# UPS.net
KiCad netlist of a schematic drawn in Altium Designer
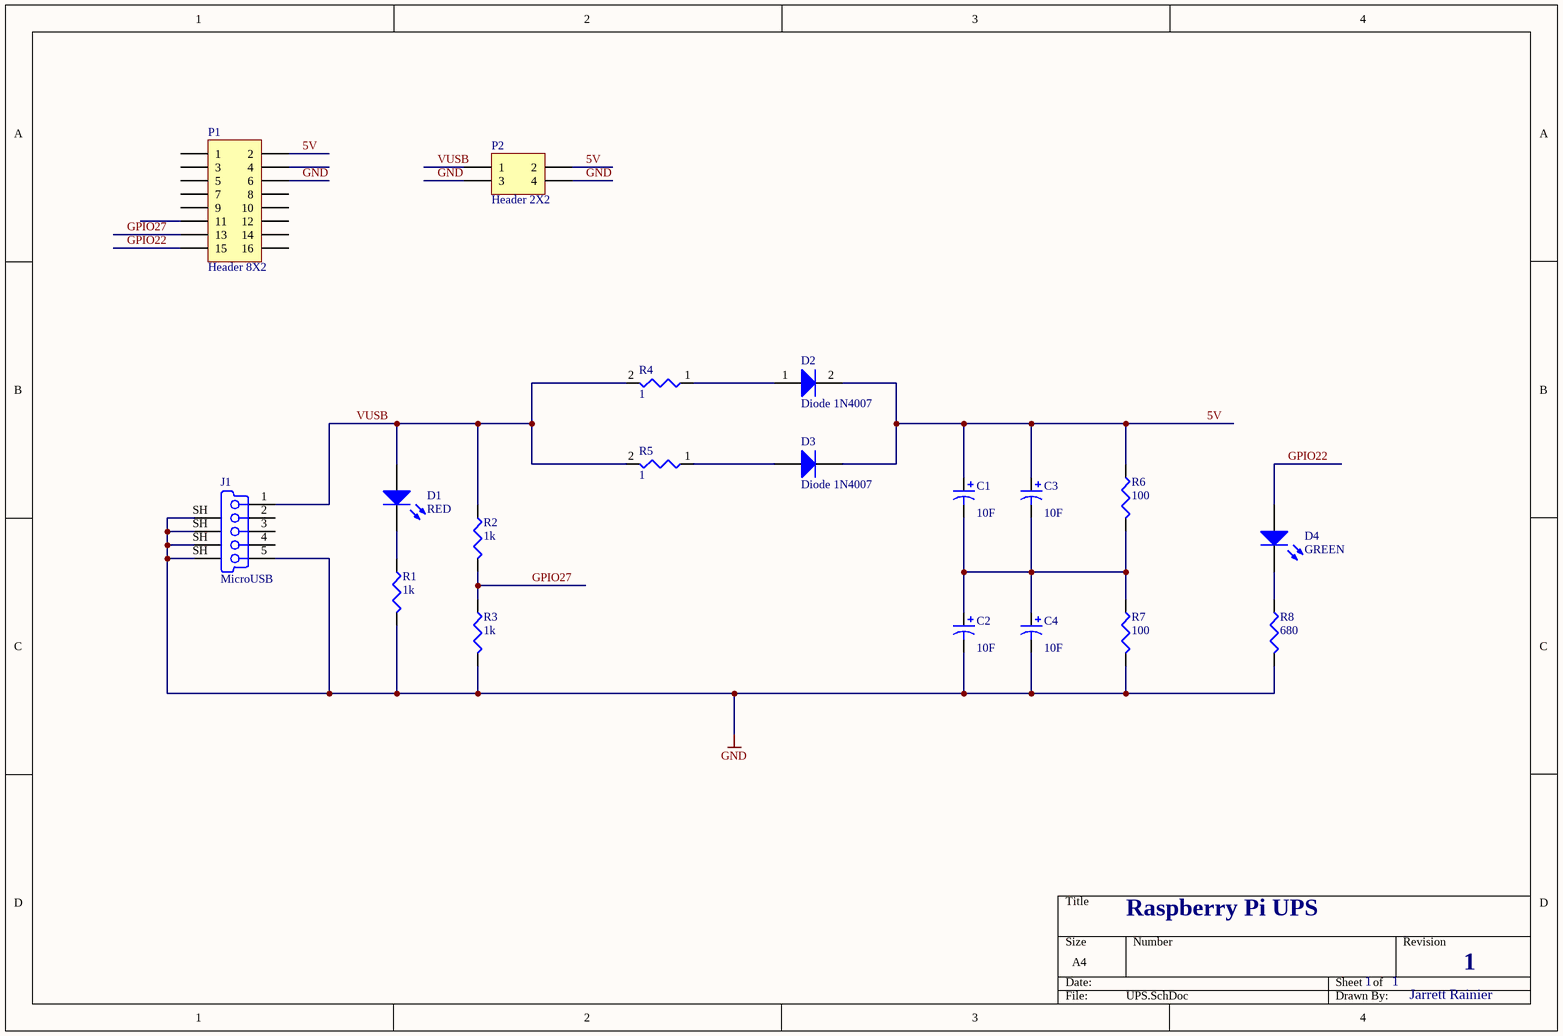
[diagram p0: UPS.SchDoc]

(export (version "E")
  (design (tool "Eeschema 10.0.6"))
  (components
    (comp (ref "C1")
      (value "10F")
      (footprint "CAPE5.0mm")
      (description "Polarized Capacitor (Radial)")
      (fields (field (name "Comment") "Cap Pol1") (field (name "PUBLISHER") "Altium Limited"))
      (libsource (lib "Miscellaneous Devices") (part "Cap Pol1"))
    )
    (comp (ref "C2")
      (value "10F")
      (footprint "CAPE5.0mm")
      (description "Polarized Capacitor (Radial)")
      (fields (field (name "Comment") "Cap Pol1") (field (name "PUBLISHER") "Altium Limited"))
      (libsource (lib "Miscellaneous Devices") (part "Cap Pol1"))
    )
    (comp (ref "C3")
      (value "10F")
      (footprint "CAPE5.0mm")
      (description "Polarized Capacitor (Radial)")
      (fields (field (name "Comment") "Cap Pol1") (field (name "PUBLISHER") "Altium Limited"))
      (libsource (lib "Miscellaneous Devices") (part "Cap Pol1"))
    )
    (comp (ref "C4")
      (value "10F")
      (footprint "CAPE5.0mm")
      (description "Polarized Capacitor (Radial)")
      (fields (field (name "Comment") "Cap Pol1") (field (name "PUBLISHER") "Altium Limited"))
      (libsource (lib "Miscellaneous Devices") (part "Cap Pol1"))
    )
    (comp (ref "D1")
      (value "RED")
      (footprint "LED_3mm")
      (description "Typical INFRARED GaAs LED")
      (fields (field (name "PUBLISHER") "Altium Limited"))
      (libsource (lib "Miscellaneous Devices") (part "LED0"))
    )
    (comp (ref "D2")
      (value "Diode 1N4007")
      (footprint "PBL - THD Packages:DO-41")
      (description "1 Amp General Purpose Rectifier")
      (fields (field (name "PUBLISHER") "Altium Limited"))
      (libsource (lib "Miscellaneous Devices") (part "Diode 1N4007"))
    )
    (comp (ref "D3")
      (value "Diode 1N4007")
      (footprint "PBL - THD Packages:DO-41")
      (description "1 Amp General Purpose Rectifier")
      (fields (field (name "PUBLISHER") "Altium Limited"))
      (libsource (lib "") (part "Diode 1N4007_1"))
    )
    (comp (ref "D4")
      (value "GREEN")
      (footprint "LED_3mm")
      (description "Typical INFRARED GaAs LED")
      (fields (field (name "PUBLISHER") "Altium Limited"))
      (libsource (lib "Miscellaneous Devices") (part "LED0"))
    )
    (comp (ref "J1")
      (value "MicroUSB")
      (footprint "USB_Micro-B_FCI_SMD")
      (fields (field (name "PUBLISHER") "Altium Limited"))
      (libsource (lib "Jarrett") (part "MicroUSB"))
    )
    (comp (ref "P1")
      (value "Header 8X2")
      (footprint "HDR2X8")
      (description "Header, 8-Pin, Dual row")
      (fields (field (name "PUBLISHER") "Altium Limited"))
      (libsource (lib "Miscellaneous Connectors") (part "Header 8X2"))
    )
    (comp (ref "P2")
      (value "Header 2X2")
      (footprint "HDR2X2")
      (description "Header, 2-Pin, Dual row")
      (fields (field (name "PUBLISHER") "Altium Limited"))
      (libsource (lib "Miscellaneous Connectors") (part "Header 2X2"))
    )
    (comp (ref "R1")
      (value "1k")
      (footprint "RESTH_0.0R_AXIAL-0.6")
      (description "Resistor")
      (fields (field (name "Comment") "Res3") (field (name "PUBLISHER") "Altium Limited"))
      (libsource (lib "Miscellaneous Devices") (part "Res3"))
    )
    (comp (ref "R2")
      (value "1k")
      (footprint "RESTH_0.0R_AXIAL-0.6")
      (description "Resistor")
      (fields (field (name "Comment") "Res3") (field (name "PUBLISHER") "Altium Limited"))
      (libsource (lib "Miscellaneous Devices") (part "Res3"))
    )
    (comp (ref "R3")
      (value "1k")
      (footprint "RESTH_0.0R_AXIAL-0.6")
      (description "Resistor")
      (fields (field (name "Comment") "Res3") (field (name "PUBLISHER") "Altium Limited"))
      (libsource (lib "Miscellaneous Devices") (part "Res3"))
    )
    (comp (ref "R4")
      (value "1")
      (footprint "RESTH_AXIAL_MRA-12")
      (description "Resistor")
      (fields (field (name "Comment") "Res3") (field (name "PUBLISHER") "Altium Limited"))
      (libsource (lib "") (part "Res3_1"))
    )
    (comp (ref "R5")
      (value "1")
      (footprint "RESTH_AXIAL_MRA-12")
      (description "Resistor")
      (fields (field (name "Comment") "Res3") (field (name "PUBLISHER") "Altium Limited"))
      (libsource (lib "") (part "Res3_1"))
    )
    (comp (ref "R6")
      (value "100")
      (footprint "RESTH_0.0R_AXIAL-0.6")
      (description "Resistor")
      (fields (field (name "Comment") "Res3") (field (name "PUBLISHER") "Altium Limited"))
      (libsource (lib "Miscellaneous Devices") (part "Res3"))
    )
    (comp (ref "R7")
      (value "100")
      (footprint "RESTH_0.0R_AXIAL-0.6")
      (description "Resistor")
      (fields (field (name "Comment") "Res3") (field (name "PUBLISHER") "Altium Limited"))
      (libsource (lib "Miscellaneous Devices") (part "Res3"))
    )
    (comp (ref "R8")
      (value "680")
      (footprint "RESTH_0.0R_AXIAL-0.6")
      (description "Resistor")
      (fields (field (name "Comment") "Res3") (field (name "PUBLISHER") "Altium Limited"))
      (libsource (lib "Miscellaneous Devices") (part "Res3"))
    )
  )
  (nets
    (net (code "1") (name "/5V") (class "Default")
      (node (ref "C1") (pin "1") (pinfunction "1_1") (pintype "passive"))
      (node (ref "C3") (pin "1") (pinfunction "1_1") (pintype "passive"))
      (node (ref "D2") (pin "2") (pinfunction "2_2") (pintype "passive"))
      (node (ref "D3") (pin "2") (pinfunction "2_2") (pintype "passive"))
      (node (ref "P1") (pin "2") (pinfunction "2_2") (pintype "passive"))
      (node (ref "P2") (pin "2") (pinfunction "2_2") (pintype "passive"))
      (node (ref "R6") (pin "1") (pinfunction "1_1") (pintype "passive"))
    )
    (net (code "2") (name "/GPIO22") (class "Default")
      (node (ref "D4") (pin "1") (pinfunction "A_1") (pintype "passive"))
      (node (ref "P1") (pin "15") (pinfunction "15_15") (pintype "passive"))
    )
    (net (code "3") (name "/GPIO27") (class "Default")
      (node (ref "P1") (pin "13") (pinfunction "13_13") (pintype "passive"))
      (node (ref "R2") (pin "2") (pinfunction "2_2") (pintype "passive"))
      (node (ref "R3") (pin "1") (pinfunction "1_1") (pintype "passive"))
    )
    (net (code "4") (name "/VUSB") (class "Default")
      (node (ref "D1") (pin "1") (pinfunction "A_1") (pintype "passive"))
      (node (ref "J1") (pin "1") (pinfunction "V_BUS_(5V)_1") (pintype "passive"))
      (node (ref "P2") (pin "1") (pinfunction "1_1") (pintype "passive"))
      (node (ref "R2") (pin "1") (pinfunction "1_1") (pintype "passive"))
      (node (ref "R4") (pin "2") (pinfunction "2_2") (pintype "passive"))
      (node (ref "R5") (pin "2") (pinfunction "2_2") (pintype "passive"))
    )
    (net (code "5") (name "GND") (class "Default")
      (node (ref "C2") (pin "2") (pinfunction "2_2") (pintype "passive"))
      (node (ref "C4") (pin "2") (pinfunction "2_2") (pintype "passive"))
      (node (ref "J1") (pin "5") (pinfunction "GND_5") (pintype "passive"))
      (node (ref "J1") (pin "SH") (pinfunction "Tab_SH") (pintype "passive"))
      (node (ref "P1") (pin "6") (pinfunction "6_6") (pintype "passive"))
      (node (ref "P2") (pin "3") (pinfunction "3_3") (pintype "passive"))
      (node (ref "P2") (pin "4") (pinfunction "4_4") (pintype "passive"))
      (node (ref "R1") (pin "2") (pinfunction "2_2") (pintype "passive"))
      (node (ref "R3") (pin "2") (pinfunction "2_2") (pintype "passive"))
      (node (ref "R7") (pin "2") (pinfunction "2_2") (pintype "passive"))
      (node (ref "R8") (pin "2") (pinfunction "2_2") (pintype "passive"))
    )
    (net (code "6") (name "Net-(C1-Pad2)") (class "Default")
      (node (ref "C1") (pin "2") (pinfunction "2_2") (pintype "passive"))
      (node (ref "C2") (pin "1") (pinfunction "1_1") (pintype "passive"))
      (node (ref "C3") (pin "2") (pinfunction "2_2") (pintype "passive"))
      (node (ref "C4") (pin "1") (pinfunction "1_1") (pintype "passive"))
      (node (ref "R6") (pin "2") (pinfunction "2_2") (pintype "passive"))
      (node (ref "R7") (pin "1") (pinfunction "1_1") (pintype "passive"))
    )
    (net (code "7") (name "Net-(D1-K)") (class "Default")
      (node (ref "D1") (pin "2") (pinfunction "K_2") (pintype "passive"))
      (node (ref "R1") (pin "1") (pinfunction "1_1") (pintype "passive"))
    )
    (net (code "8") (name "Net-(D2-Pad1)") (class "Default")
      (node (ref "D2") (pin "1") (pinfunction "1_1") (pintype "passive"))
      (node (ref "R4") (pin "1") (pinfunction "1_1") (pintype "passive"))
    )
    (net (code "9") (name "Net-(D3-Pad1)") (class "Default")
      (node (ref "D3") (pin "1") (pinfunction "1_1") (pintype "passive"))
      (node (ref "R5") (pin "1") (pinfunction "1_1") (pintype "passive"))
    )
    (net (code "10") (name "Net-(D4-K)") (class "Default")
      (node (ref "D4") (pin "2") (pinfunction "K_2") (pintype "passive"))
      (node (ref "R8") (pin "1") (pinfunction "1_1") (pintype "passive"))
    )
    (net (code "11") (name "unconnected-(J1-D+-Pad3)") (class "Default")
      (node (ref "J1") (pin "3") (pinfunction "D+_3") (pintype "passive"))
    )
    (net (code "12") (name "unconnected-(J1-D--Pad2)") (class "Default")
      (node (ref "J1") (pin "2") (pinfunction "D-_2") (pintype "passive"))
    )
    (net (code "13") (name "unconnected-(J1-NC-Pad4)") (class "Default")
      (node (ref "J1") (pin "4") (pinfunction "NC_4") (pintype "passive"))
    )
    (net (code "14") (name "unconnected-(P1-Pad1)") (class "Default")
      (node (ref "P1") (pin "1") (pinfunction "1_1") (pintype "passive"))
    )
    (net (code "15") (name "unconnected-(P1-Pad3)") (class "Default")
      (node (ref "P1") (pin "3") (pinfunction "3_3") (pintype "passive"))
    )
    (net (code "16") (name "unconnected-(P1-Pad4)") (class "Default")
      (node (ref "P1") (pin "4") (pinfunction "4_4") (pintype "passive"))
    )
    (net (code "17") (name "unconnected-(P1-Pad5)") (class "Default")
      (node (ref "P1") (pin "5") (pinfunction "5_5") (pintype "passive"))
    )
    (net (code "18") (name "unconnected-(P1-Pad7)") (class "Default")
      (node (ref "P1") (pin "7") (pinfunction "7_7") (pintype "passive"))
    )
    (net (code "19") (name "unconnected-(P1-Pad8)") (class "Default")
      (node (ref "P1") (pin "8") (pinfunction "8_8") (pintype "passive"))
    )
    (net (code "20") (name "unconnected-(P1-Pad9)") (class "Default")
      (node (ref "P1") (pin "9") (pinfunction "9_9") (pintype "passive"))
    )
    (net (code "21") (name "unconnected-(P1-Pad10)") (class "Default")
      (node (ref "P1") (pin "10") (pinfunction "10_10") (pintype "passive"))
    )
    (net (code "22") (name "unconnected-(P1-Pad11)") (class "Default")
      (node (ref "P1") (pin "11") (pinfunction "11_11") (pintype "passive"))
    )
    (net (code "23") (name "unconnected-(P1-Pad12)") (class "Default")
      (node (ref "P1") (pin "12") (pinfunction "12_12") (pintype "passive"))
    )
    (net (code "24") (name "unconnected-(P1-Pad14)") (class "Default")
      (node (ref "P1") (pin "14") (pinfunction "14_14") (pintype "passive"))
    )
    (net (code "25") (name "unconnected-(P1-Pad16)") (class "Default")
      (node (ref "P1") (pin "16") (pinfunction "16_16") (pintype "passive"))
    )
  )
)
